# controller.net
KiCad netlist of a schematic drawn in EAGLE
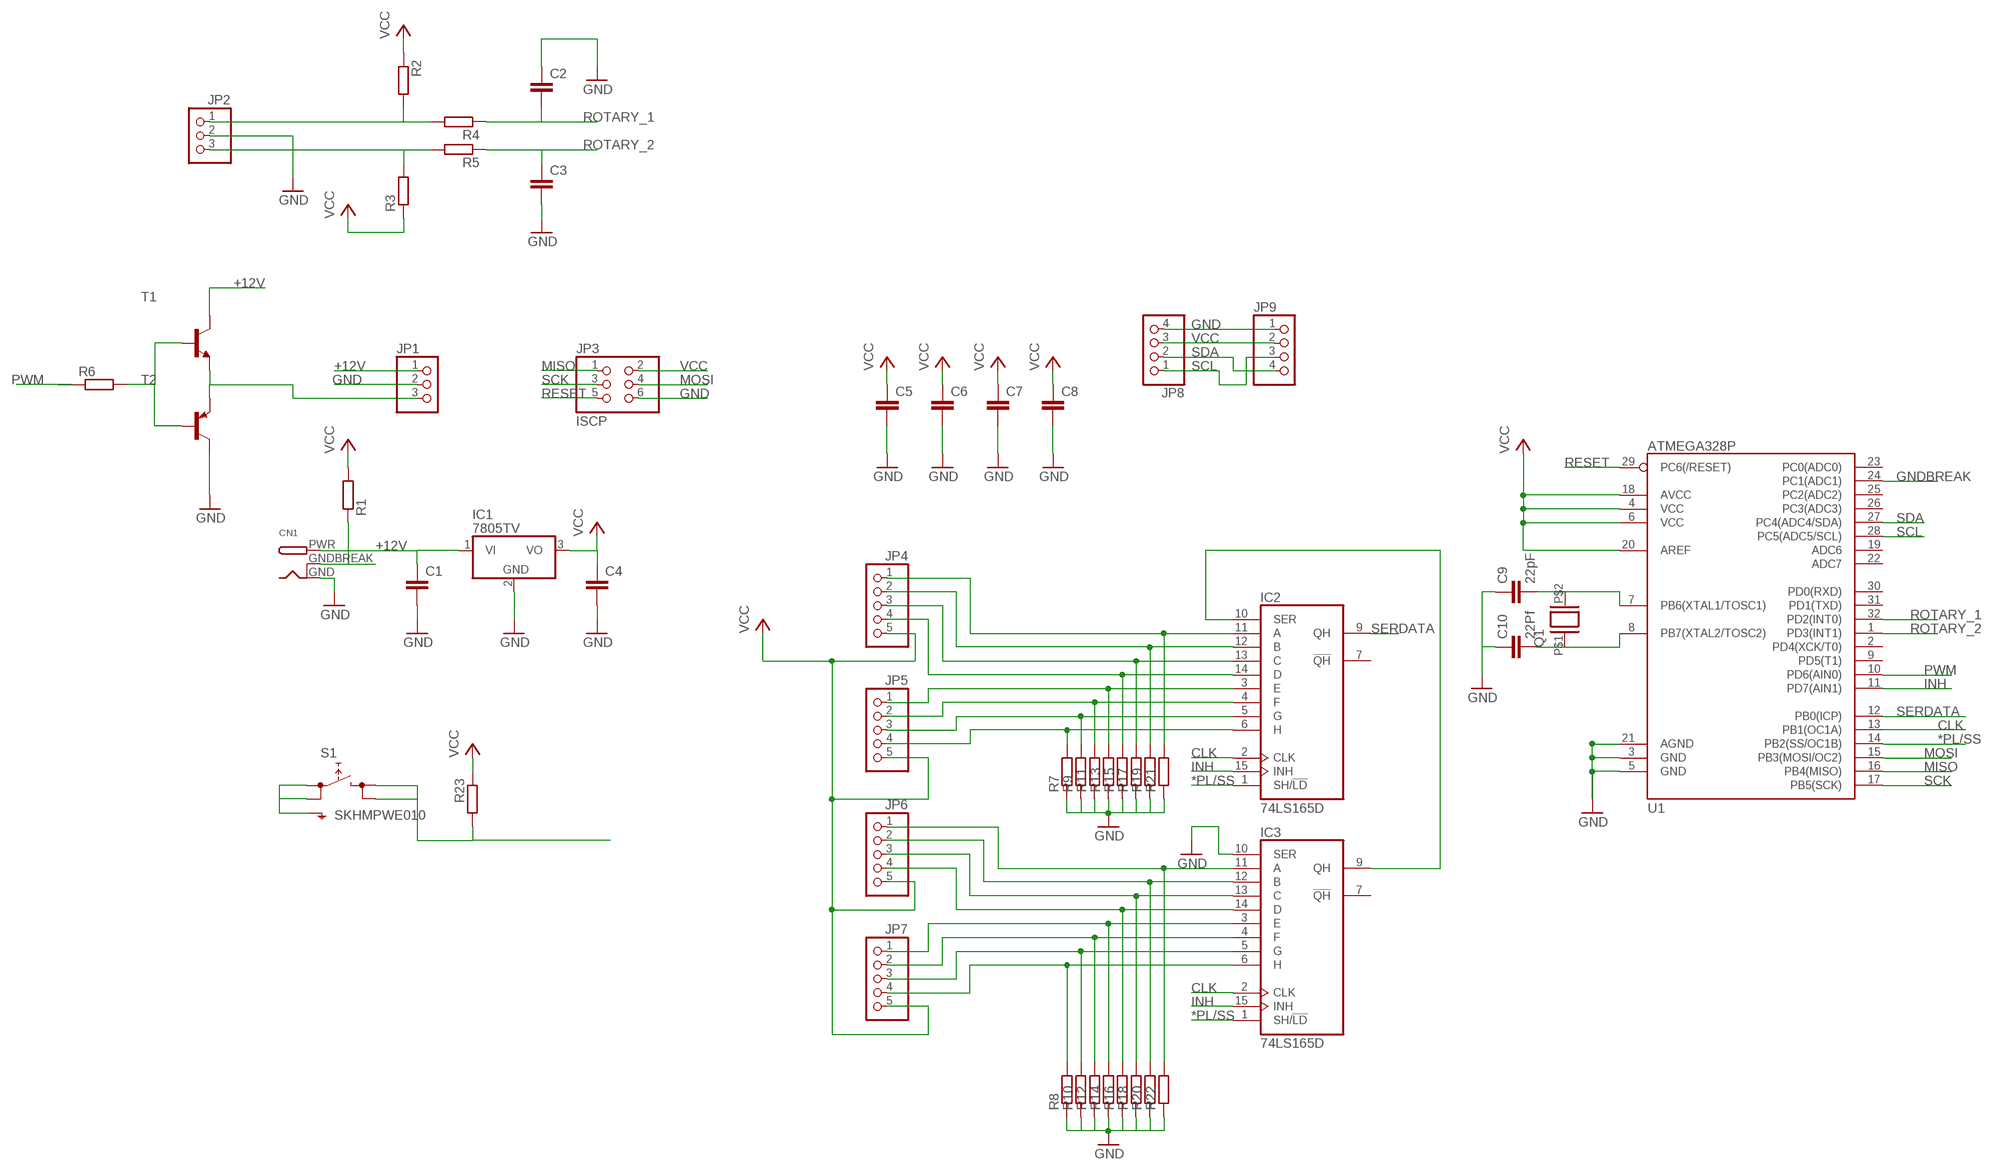
[diagram p0: schematic, sheet 1]

(export (version "E")
  (design (tool "Eeschema 10.0.6"))
  (components
    (comp (ref "C1")
      (value "C-EUC0805")
      (footprint "eagle-import:C0805")
      (libsource (lib "eagle-import") (part "C-EUC0805"))
    )
    (comp (ref "C2")
      (value "C-EUC0805")
      (footprint "eagle-import:C0805")
      (libsource (lib "eagle-import") (part "C-EUC0805"))
    )
    (comp (ref "C3")
      (value "C-EUC0805")
      (footprint "eagle-import:C0805")
      (libsource (lib "eagle-import") (part "C-EUC0805"))
    )
    (comp (ref "C4")
      (value "C-EUC0805")
      (footprint "eagle-import:C0805")
      (libsource (lib "eagle-import") (part "C-EUC0805"))
    )
    (comp (ref "C5")
      (value "C-EUC0805")
      (footprint "eagle-import:C0805")
      (libsource (lib "eagle-import") (part "C-EUC0805"))
    )
    (comp (ref "C6")
      (value "C-EUC0805")
      (footprint "eagle-import:C0805")
      (libsource (lib "eagle-import") (part "C-EUC0805"))
    )
    (comp (ref "C7")
      (value "C-EUC0805")
      (footprint "eagle-import:C0805")
      (libsource (lib "eagle-import") (part "C-EUC0805"))
    )
    (comp (ref "C8")
      (value "C-EUC0805")
      (footprint "eagle-import:C0805")
      (libsource (lib "eagle-import") (part "C-EUC0805"))
    )
    (comp (ref "C9")
      (value "22pF")
      (footprint "eagle-import:C0805")
      (libsource (lib "eagle-import") (part "C-EUC0805"))
    )
    (comp (ref "C10")
      (value "22Pf")
      (footprint "eagle-import:C0805")
      (libsource (lib "eagle-import") (part "C-EUC0805"))
    )
    (comp (ref "CN1")
      (value "DCBARRELPTH")
      (footprint "eagle-import:DCJACK_2MM_PTH")
      (libsource (lib "eagle-import") (part "DCBARRELPTH"))
    )
    (comp (ref "IC1")
      (value "7805TV")
      (footprint "eagle-import:TO220V")
      (libsource (lib "eagle-import") (part "78TV05"))
    )
    (comp (ref "IC2")
      (value "74LS165D")
      (footprint "eagle-import:SO16")
      (libsource (lib "eagle-import") (part "74165DLS"))
    )
    (comp (ref "IC3")
      (value "74LS165D")
      (footprint "eagle-import:SO16")
      (libsource (lib "eagle-import") (part "74165DLS"))
    )
    (comp (ref "JP1")
      (value "PINHD-1X3")
      (footprint "eagle-import:1X03")
      (libsource (lib "eagle-import") (part "PINHD-1X3"))
    )
    (comp (ref "JP2")
      (value "PINHD-1X3")
      (footprint "eagle-import:1X03")
      (libsource (lib "eagle-import") (part "PINHD-1X3"))
    )
    (comp (ref "JP3")
      (value "ISCP")
      (footprint "eagle-import:2X03")
      (libsource (lib "eagle-import") (part "PINHD-2X3"))
    )
    (comp (ref "JP4")
      (value "PINHD-1X5")
      (footprint "eagle-import:1X05")
      (libsource (lib "eagle-import") (part "PINHD-1X5"))
    )
    (comp (ref "JP5")
      (value "PINHD-1X5")
      (footprint "eagle-import:1X05")
      (libsource (lib "eagle-import") (part "PINHD-1X5"))
    )
    (comp (ref "JP6")
      (value "PINHD-1X5")
      (footprint "eagle-import:1X05")
      (libsource (lib "eagle-import") (part "PINHD-1X5"))
    )
    (comp (ref "JP7")
      (value "PINHD-1X5")
      (footprint "eagle-import:1X05")
      (libsource (lib "eagle-import") (part "PINHD-1X5"))
    )
    (comp (ref "JP8")
      (value "PINHD-1X4")
      (footprint "eagle-import:1X04")
      (libsource (lib "eagle-import") (part "PINHD-1X4"))
    )
    (comp (ref "JP9")
      (value "PINHD-1X4")
      (footprint "eagle-import:1X04")
      (libsource (lib "eagle-import") (part "PINHD-1X4"))
    )
    (comp (ref "Q1")
      (value "XTAL")
      (footprint "eagle-import:CSM-3X")
      (libsource (lib "eagle-import") (part "XTAL"))
    )
    (comp (ref "R1")
      (value "R-EU_R0805")
      (footprint "eagle-import:R0805")
      (libsource (lib "eagle-import") (part "R-EU_R0805"))
    )
    (comp (ref "R2")
      (value "R-EU_R0805")
      (footprint "eagle-import:R0805")
      (libsource (lib "eagle-import") (part "R-EU_R0805"))
    )
    (comp (ref "R3")
      (value "R-EU_R0805")
      (footprint "eagle-import:R0805")
      (libsource (lib "eagle-import") (part "R-EU_R0805"))
    )
    (comp (ref "R4")
      (value "R-EU_R0805")
      (footprint "eagle-import:R0805")
      (libsource (lib "eagle-import") (part "R-EU_R0805"))
    )
    (comp (ref "R5")
      (value "R-EU_R0805")
      (footprint "eagle-import:R0805")
      (libsource (lib "eagle-import") (part "R-EU_R0805"))
    )
    (comp (ref "R6")
      (value "R-EU_R0805")
      (footprint "eagle-import:R0805")
      (libsource (lib "eagle-import") (part "R-EU_R0805"))
    )
    (comp (ref "R7")
      (value "R-EU_R0805")
      (footprint "eagle-import:R0805")
      (libsource (lib "eagle-import") (part "R-EU_R0805"))
    )
    (comp (ref "R8")
      (value "R-EU_R0805")
      (footprint "eagle-import:R0805")
      (libsource (lib "eagle-import") (part "R-EU_R0805"))
    )
    (comp (ref "R9")
      (value "R-EU_R0805")
      (footprint "eagle-import:R0805")
      (libsource (lib "eagle-import") (part "R-EU_R0805"))
    )
    (comp (ref "R10")
      (value "R-EU_R0805")
      (footprint "eagle-import:R0805")
      (libsource (lib "eagle-import") (part "R-EU_R0805"))
    )
    (comp (ref "R11")
      (value "R-EU_R0805")
      (footprint "eagle-import:R0805")
      (libsource (lib "eagle-import") (part "R-EU_R0805"))
    )
    (comp (ref "R12")
      (value "R-EU_R0805")
      (footprint "eagle-import:R0805")
      (libsource (lib "eagle-import") (part "R-EU_R0805"))
    )
    (comp (ref "R13")
      (value "R-EU_R0805")
      (footprint "eagle-import:R0805")
      (libsource (lib "eagle-import") (part "R-EU_R0805"))
    )
    (comp (ref "R14")
      (value "R-EU_R0805")
      (footprint "eagle-import:R0805")
      (libsource (lib "eagle-import") (part "R-EU_R0805"))
    )
    (comp (ref "R15")
      (value "R-EU_R0805")
      (footprint "eagle-import:R0805")
      (libsource (lib "eagle-import") (part "R-EU_R0805"))
    )
    (comp (ref "R16")
      (value "R-EU_R0805")
      (footprint "eagle-import:R0805")
      (libsource (lib "eagle-import") (part "R-EU_R0805"))
    )
    (comp (ref "R17")
      (value "R-EU_R0805")
      (footprint "eagle-import:R0805")
      (libsource (lib "eagle-import") (part "R-EU_R0805"))
    )
    (comp (ref "R18")
      (value "R-EU_R0805")
      (footprint "eagle-import:R0805")
      (libsource (lib "eagle-import") (part "R-EU_R0805"))
    )
    (comp (ref "R19")
      (value "R-EU_R0805")
      (footprint "eagle-import:R0805")
      (libsource (lib "eagle-import") (part "R-EU_R0805"))
    )
    (comp (ref "R20")
      (value "R-EU_R0805")
      (footprint "eagle-import:R0805")
      (libsource (lib "eagle-import") (part "R-EU_R0805"))
    )
    (comp (ref "R21")
      (value "R-EU_R0805")
      (footprint "eagle-import:R0805")
      (libsource (lib "eagle-import") (part "R-EU_R0805"))
    )
    (comp (ref "R22")
      (value "R-EU_R0805")
      (footprint "eagle-import:R0805")
      (libsource (lib "eagle-import") (part "R-EU_R0805"))
    )
    (comp (ref "R23")
      (value "R-EU_R0805")
      (footprint "eagle-import:R0805")
      (libsource (lib "eagle-import") (part "R-EU_R0805"))
    )
    (comp (ref "S1")
      (value "SKHMPWE010")
      (footprint "eagle-import:SKHMPXE010")
      (libsource (lib "eagle-import") (part "SKHMPE010W"))
    )
    (comp (ref "T1")
      (value "BC847-NPN-SOT23-BEC")
      (footprint "eagle-import:SOT23-BEC")
      (libsource (lib "eagle-import") (part "-NPN-SOT23-BECBC847"))
    )
    (comp (ref "T2")
      (value "BC807-16-PNP-SOT23-BEC")
      (footprint "eagle-import:SOT23-BEC")
      (libsource (lib "eagle-import") (part "-PNP-SOT23-BECBC807-16"))
    )
    (comp (ref "U1")
      (value "ATMEGA328P")
      (footprint "eagle-import:TQFP32-08")
      (libsource (lib "eagle-import") (part "ATMEGA328_SMT"))
    )
  )
  (nets
    (net (code "1") (name "/*PL{slash}SS") (class "Default")
      (node (ref "IC2") (pin "1") (pinfunction "SH/~{LD}_1") (pintype "input"))
      (node (ref "IC3") (pin "1") (pinfunction "SH/~{LD}_1") (pintype "input"))
      (node (ref "U1") (pin "14") (pinfunction "PB2(SS/OC1B)_14") (pintype "bidirectional"))
    )
    (net (code "2") (name "/+12V") (class "Default")
      (node (ref "C1") (pin "1") (pinfunction "1_1") (pintype "passive"))
      (node (ref "CN1") (pin "PWR") (pinfunction "PWR_PWR") (pintype "power_in"))
      (node (ref "IC1") (pin "1") (pinfunction "VI_1") (pintype "input"))
      (node (ref "JP1") (pin "1") (pinfunction "1_1") (pintype "passive"))
      (node (ref "T1") (pin "C") (pinfunction "C_C") (pintype "passive"))
    )
    (net (code "3") (name "/CLK") (class "Default")
      (node (ref "IC2") (pin "2") (pinfunction "CLK_2") (pintype "input"))
      (node (ref "IC3") (pin "2") (pinfunction "CLK_2") (pintype "input"))
      (node (ref "U1") (pin "13") (pinfunction "PB1(OC1A)_13") (pintype "bidirectional"))
    )
    (net (code "4") (name "/GNDBREAK") (class "Default")
      (node (ref "CN1") (pin "GNDBREAK") (pinfunction "GNDBREAK_GNDBREAK") (pintype "power_in"))
      (node (ref "R1") (pin "1") (pinfunction "1_1") (pintype "passive"))
      (node (ref "U1") (pin "24") (pinfunction "PC1(ADC1)_24") (pintype "bidirectional"))
    )
    (net (code "5") (name "/INH") (class "Default")
      (node (ref "IC2") (pin "15") (pinfunction "INH_15") (pintype "input"))
      (node (ref "IC3") (pin "15") (pinfunction "INH_15") (pintype "input"))
      (node (ref "U1") (pin "11") (pinfunction "PD7(AIN1)_11") (pintype "bidirectional"))
    )
    (net (code "6") (name "/MISO") (class "Default")
      (node (ref "JP3") (pin "1") (pinfunction "1_1") (pintype "passive"))
      (node (ref "U1") (pin "16") (pinfunction "PB4(MISO)_16") (pintype "bidirectional"))
    )
    (net (code "7") (name "/MOSI") (class "Default")
      (node (ref "JP3") (pin "4") (pinfunction "4_4") (pintype "passive"))
      (node (ref "U1") (pin "15") (pinfunction "PB3(MOSI/OC2)_15") (pintype "bidirectional"))
    )
    (net (code "8") (name "/PWM") (class "Default")
      (node (ref "R6") (pin "1") (pinfunction "1_1") (pintype "passive"))
      (node (ref "U1") (pin "10") (pinfunction "PD6(AIN0)_10") (pintype "bidirectional"))
    )
    (net (code "9") (name "/RESET") (class "Default")
      (node (ref "JP3") (pin "5") (pinfunction "5_5") (pintype "passive"))
      (node (ref "R23") (pin "2") (pinfunction "2_2") (pintype "passive"))
      (node (ref "S1") (pin "3") (pinfunction "2.1_3") (pintype "passive"))
      (node (ref "S1") (pin "4") (pinfunction "2.2_4") (pintype "passive"))
      (node (ref "U1") (pin "29") (pinfunction "PC6(/RESET)_29") (pintype "bidirectional"))
    )
    (net (code "10") (name "/ROTARY_1") (class "Default")
      (node (ref "C2") (pin "2") (pinfunction "2_2") (pintype "passive"))
      (node (ref "R4") (pin "1") (pinfunction "1_1") (pintype "passive"))
      (node (ref "U1") (pin "32") (pinfunction "PD2(INT0)_32") (pintype "bidirectional"))
    )
    (net (code "11") (name "/ROTARY_2") (class "Default")
      (node (ref "C3") (pin "1") (pinfunction "1_1") (pintype "passive"))
      (node (ref "R5") (pin "1") (pinfunction "1_1") (pintype "passive"))
      (node (ref "U1") (pin "1") (pinfunction "PD3(INT1)_1") (pintype "bidirectional"))
    )
    (net (code "12") (name "/SCK") (class "Default")
      (node (ref "JP3") (pin "3") (pinfunction "3_3") (pintype "passive"))
      (node (ref "U1") (pin "17") (pinfunction "PB5(SCK)_17") (pintype "bidirectional"))
    )
    (net (code "13") (name "/SCL") (class "Default")
      (node (ref "JP8") (pin "1") (pinfunction "1_1") (pintype "passive"))
      (node (ref "JP9") (pin "3") (pinfunction "3_3") (pintype "passive"))
      (node (ref "U1") (pin "28") (pinfunction "PC5(ADC5/SCL)_28") (pintype "bidirectional"))
    )
    (net (code "14") (name "/SDA") (class "Default")
      (node (ref "JP8") (pin "2") (pinfunction "2_2") (pintype "passive"))
      (node (ref "JP9") (pin "4") (pinfunction "4_4") (pintype "passive"))
      (node (ref "U1") (pin "27") (pinfunction "PC4(ADC4/SDA)_27") (pintype "bidirectional"))
    )
    (net (code "15") (name "/SERDATA") (class "Default")
      (node (ref "IC2") (pin "9") (pinfunction "QH_9") (pintype "output"))
      (node (ref "U1") (pin "12") (pinfunction "PB0(ICP)_12") (pintype "bidirectional"))
    )
    (net (code "16") (name "GND") (class "Default")
      (node (ref "C1") (pin "2") (pinfunction "2_2") (pintype "passive"))
      (node (ref "C10") (pin "1") (pinfunction "1_1") (pintype "passive"))
      (node (ref "C2") (pin "1") (pinfunction "1_1") (pintype "passive"))
      (node (ref "C3") (pin "2") (pinfunction "2_2") (pintype "passive"))
      (node (ref "C4") (pin "2") (pinfunction "2_2") (pintype "passive"))
      (node (ref "C5") (pin "2") (pinfunction "2_2") (pintype "passive"))
      (node (ref "C6") (pin "2") (pinfunction "2_2") (pintype "passive"))
      (node (ref "C7") (pin "2") (pinfunction "2_2") (pintype "passive"))
      (node (ref "C8") (pin "2") (pinfunction "2_2") (pintype "passive"))
      (node (ref "C9") (pin "1") (pinfunction "1_1") (pintype "passive"))
      (node (ref "CN1") (pin "GND") (pinfunction "GND_GND") (pintype "power_in"))
      (node (ref "IC1") (pin "2") (pinfunction "GND_2") (pintype "passive"))
      (node (ref "IC3") (pin "10") (pinfunction "SER_10") (pintype "input"))
      (node (ref "JP1") (pin "2") (pinfunction "2_2") (pintype "passive"))
      (node (ref "JP2") (pin "2") (pinfunction "2_2") (pintype "passive"))
      (node (ref "JP3") (pin "6") (pinfunction "6_6") (pintype "passive"))
      (node (ref "JP8") (pin "4") (pinfunction "4_4") (pintype "passive"))
      (node (ref "JP9") (pin "1") (pinfunction "1_1") (pintype "passive"))
      (node (ref "R10") (pin "1") (pinfunction "1_1") (pintype "passive"))
      (node (ref "R11") (pin "1") (pinfunction "1_1") (pintype "passive"))
      (node (ref "R12") (pin "1") (pinfunction "1_1") (pintype "passive"))
      (node (ref "R13") (pin "1") (pinfunction "1_1") (pintype "passive"))
      (node (ref "R14") (pin "1") (pinfunction "1_1") (pintype "passive"))
      (node (ref "R15") (pin "1") (pinfunction "1_1") (pintype "passive"))
      (node (ref "R16") (pin "1") (pinfunction "1_1") (pintype "passive"))
      (node (ref "R17") (pin "1") (pinfunction "1_1") (pintype "passive"))
      (node (ref "R18") (pin "1") (pinfunction "1_1") (pintype "passive"))
      (node (ref "R19") (pin "1") (pinfunction "1_1") (pintype "passive"))
      (node (ref "R20") (pin "1") (pinfunction "1_1") (pintype "passive"))
      (node (ref "R21") (pin "1") (pinfunction "1_1") (pintype "passive"))
      (node (ref "R22") (pin "1") (pinfunction "1_1") (pintype "passive"))
      (node (ref "R7") (pin "1") (pinfunction "1_1") (pintype "passive"))
      (node (ref "R8") (pin "1") (pinfunction "1_1") (pintype "passive"))
      (node (ref "R9") (pin "1") (pinfunction "1_1") (pintype "passive"))
      (node (ref "S1") (pin "1") (pinfunction "1.1_1") (pintype "passive"))
      (node (ref "S1") (pin "2") (pinfunction "1.2_2") (pintype "passive"))
      (node (ref "S1") (pin "5") (pinfunction "SH_5") (pintype "passive"))
      (node (ref "T2") (pin "C") (pinfunction "C_C") (pintype "passive"))
      (node (ref "U1") (pin "21") (pinfunction "AGND_21") (pintype "bidirectional"))
      (node (ref "U1") (pin "3") (pinfunction "GND_3") (pintype "bidirectional"))
      (node (ref "U1") (pin "5") (pinfunction "GND_5") (pintype "bidirectional"))
    )
    (net (code "17") (name "Net-(IC2A-A)") (class "Default")
      (node (ref "IC2") (pin "11") (pinfunction "A_11") (pintype "input"))
      (node (ref "JP4") (pin "1") (pinfunction "1_1") (pintype "passive"))
      (node (ref "R21") (pin "2") (pinfunction "2_2") (pintype "passive"))
    )
    (net (code "18") (name "Net-(IC2A-B)") (class "Default")
      (node (ref "IC2") (pin "12") (pinfunction "B_12") (pintype "input"))
      (node (ref "JP4") (pin "2") (pinfunction "2_2") (pintype "passive"))
      (node (ref "R19") (pin "2") (pinfunction "2_2") (pintype "passive"))
    )
    (net (code "19") (name "Net-(IC2A-C)") (class "Default")
      (node (ref "IC2") (pin "13") (pinfunction "C_13") (pintype "input"))
      (node (ref "JP4") (pin "3") (pinfunction "3_3") (pintype "passive"))
      (node (ref "R17") (pin "2") (pinfunction "2_2") (pintype "passive"))
    )
    (net (code "20") (name "Net-(IC2A-D)") (class "Default")
      (node (ref "IC2") (pin "14") (pinfunction "D_14") (pintype "input"))
      (node (ref "JP4") (pin "4") (pinfunction "4_4") (pintype "passive"))
      (node (ref "R15") (pin "2") (pinfunction "2_2") (pintype "passive"))
    )
    (net (code "21") (name "Net-(IC2A-E)") (class "Default")
      (node (ref "IC2") (pin "3") (pinfunction "E_3") (pintype "input"))
      (node (ref "JP5") (pin "1") (pinfunction "1_1") (pintype "passive"))
      (node (ref "R13") (pin "2") (pinfunction "2_2") (pintype "passive"))
    )
    (net (code "22") (name "Net-(IC2A-F)") (class "Default")
      (node (ref "IC2") (pin "4") (pinfunction "F_4") (pintype "input"))
      (node (ref "JP5") (pin "2") (pinfunction "2_2") (pintype "passive"))
      (node (ref "R11") (pin "2") (pinfunction "2_2") (pintype "passive"))
    )
    (net (code "23") (name "Net-(IC2A-G)") (class "Default")
      (node (ref "IC2") (pin "5") (pinfunction "G_5") (pintype "input"))
      (node (ref "JP5") (pin "3") (pinfunction "3_3") (pintype "passive"))
      (node (ref "R9") (pin "2") (pinfunction "2_2") (pintype "passive"))
    )
    (net (code "24") (name "Net-(IC2A-H)") (class "Default")
      (node (ref "IC2") (pin "6") (pinfunction "H_6") (pintype "input"))
      (node (ref "JP5") (pin "4") (pinfunction "4_4") (pintype "passive"))
      (node (ref "R7") (pin "2") (pinfunction "2_2") (pintype "passive"))
    )
    (net (code "25") (name "Net-(IC2A-SER)") (class "Default")
      (node (ref "IC2") (pin "10") (pinfunction "SER_10") (pintype "input"))
      (node (ref "IC3") (pin "9") (pinfunction "QH_9") (pintype "output"))
    )
    (net (code "26") (name "Net-(IC3A-A)") (class "Default")
      (node (ref "IC3") (pin "11") (pinfunction "A_11") (pintype "input"))
      (node (ref "JP6") (pin "1") (pinfunction "1_1") (pintype "passive"))
      (node (ref "R22") (pin "2") (pinfunction "2_2") (pintype "passive"))
    )
    (net (code "27") (name "Net-(IC3A-B)") (class "Default")
      (node (ref "IC3") (pin "12") (pinfunction "B_12") (pintype "input"))
      (node (ref "JP6") (pin "2") (pinfunction "2_2") (pintype "passive"))
      (node (ref "R20") (pin "2") (pinfunction "2_2") (pintype "passive"))
    )
    (net (code "28") (name "Net-(IC3A-C)") (class "Default")
      (node (ref "IC3") (pin "13") (pinfunction "C_13") (pintype "input"))
      (node (ref "JP6") (pin "3") (pinfunction "3_3") (pintype "passive"))
      (node (ref "R18") (pin "2") (pinfunction "2_2") (pintype "passive"))
    )
    (net (code "29") (name "Net-(IC3A-D)") (class "Default")
      (node (ref "IC3") (pin "14") (pinfunction "D_14") (pintype "input"))
      (node (ref "JP6") (pin "4") (pinfunction "4_4") (pintype "passive"))
      (node (ref "R16") (pin "2") (pinfunction "2_2") (pintype "passive"))
    )
    (net (code "30") (name "Net-(IC3A-E)") (class "Default")
      (node (ref "IC3") (pin "3") (pinfunction "E_3") (pintype "input"))
      (node (ref "JP7") (pin "1") (pinfunction "1_1") (pintype "passive"))
      (node (ref "R14") (pin "2") (pinfunction "2_2") (pintype "passive"))
    )
    (net (code "31") (name "Net-(IC3A-F)") (class "Default")
      (node (ref "IC3") (pin "4") (pinfunction "F_4") (pintype "input"))
      (node (ref "JP7") (pin "2") (pinfunction "2_2") (pintype "passive"))
      (node (ref "R12") (pin "2") (pinfunction "2_2") (pintype "passive"))
    )
    (net (code "32") (name "Net-(IC3A-G)") (class "Default")
      (node (ref "IC3") (pin "5") (pinfunction "G_5") (pintype "input"))
      (node (ref "JP7") (pin "3") (pinfunction "3_3") (pintype "passive"))
      (node (ref "R10") (pin "2") (pinfunction "2_2") (pintype "passive"))
    )
    (net (code "33") (name "Net-(IC3A-H)") (class "Default")
      (node (ref "IC3") (pin "6") (pinfunction "H_6") (pintype "input"))
      (node (ref "JP7") (pin "4") (pinfunction "4_4") (pintype "passive"))
      (node (ref "R8") (pin "2") (pinfunction "2_2") (pintype "passive"))
    )
    (net (code "34") (name "Net-(JP1-Pad3)") (class "Default")
      (node (ref "JP1") (pin "3") (pinfunction "3_3") (pintype "passive"))
      (node (ref "T1") (pin "E") (pinfunction "E_E") (pintype "passive"))
      (node (ref "T2") (pin "E") (pinfunction "E_E") (pintype "passive"))
    )
    (net (code "35") (name "Net-(JP2-Pad1)") (class "Default")
      (node (ref "JP2") (pin "1") (pinfunction "1_1") (pintype "passive"))
      (node (ref "R2") (pin "2") (pinfunction "2_2") (pintype "passive"))
      (node (ref "R4") (pin "2") (pinfunction "2_2") (pintype "passive"))
    )
    (net (code "36") (name "Net-(JP2-Pad3)") (class "Default")
      (node (ref "JP2") (pin "3") (pinfunction "3_3") (pintype "passive"))
      (node (ref "R3") (pin "2") (pinfunction "2_2") (pintype "passive"))
      (node (ref "R5") (pin "2") (pinfunction "2_2") (pintype "passive"))
    )
    (net (code "37") (name "Net-(Q1-1)") (class "Default")
      (node (ref "C10") (pin "2") (pinfunction "2_2") (pintype "passive"))
      (node (ref "Q1") (pin "P$1") (pinfunction "1_P$1") (pintype "passive"))
      (node (ref "U1") (pin "8") (pinfunction "PB7(XTAL2/TOSC2)_8") (pintype "bidirectional"))
    )
    (net (code "38") (name "Net-(Q1-2)") (class "Default")
      (node (ref "C9") (pin "2") (pinfunction "2_2") (pintype "passive"))
      (node (ref "Q1") (pin "P$2") (pinfunction "2_P$2") (pintype "passive"))
      (node (ref "U1") (pin "7") (pinfunction "PB6(XTAL1/TOSC1)_7") (pintype "bidirectional"))
    )
    (net (code "39") (name "Net-(R6-Pad2)") (class "Default")
      (node (ref "R6") (pin "2") (pinfunction "2_2") (pintype "passive"))
      (node (ref "T1") (pin "B") (pinfunction "B_B") (pintype "passive"))
      (node (ref "T2") (pin "B") (pinfunction "B_B") (pintype "passive"))
    )
    (net (code "40") (name "VCC") (class "Default")
      (node (ref "C4") (pin "1") (pinfunction "1_1") (pintype "passive"))
      (node (ref "C5") (pin "1") (pinfunction "1_1") (pintype "passive"))
      (node (ref "C6") (pin "1") (pinfunction "1_1") (pintype "passive"))
      (node (ref "C7") (pin "1") (pinfunction "1_1") (pintype "passive"))
      (node (ref "C8") (pin "1") (pinfunction "1_1") (pintype "passive"))
      (node (ref "IC1") (pin "3") (pinfunction "VO_3") (pintype "passive"))
      (node (ref "JP3") (pin "2") (pinfunction "2_2") (pintype "passive"))
      (node (ref "JP4") (pin "5") (pinfunction "5_5") (pintype "passive"))
      (node (ref "JP5") (pin "5") (pinfunction "5_5") (pintype "passive"))
      (node (ref "JP6") (pin "5") (pinfunction "5_5") (pintype "passive"))
      (node (ref "JP7") (pin "5") (pinfunction "5_5") (pintype "passive"))
      (node (ref "JP8") (pin "3") (pinfunction "3_3") (pintype "passive"))
      (node (ref "JP9") (pin "2") (pinfunction "2_2") (pintype "passive"))
      (node (ref "R1") (pin "2") (pinfunction "2_2") (pintype "passive"))
      (node (ref "R2") (pin "1") (pinfunction "1_1") (pintype "passive"))
      (node (ref "R23") (pin "1") (pinfunction "1_1") (pintype "passive"))
      (node (ref "R3") (pin "1") (pinfunction "1_1") (pintype "passive"))
      (node (ref "U1") (pin "18") (pinfunction "AVCC_18") (pintype "bidirectional"))
      (node (ref "U1") (pin "20") (pinfunction "AREF_20") (pintype "bidirectional"))
      (node (ref "U1") (pin "4") (pinfunction "VCC_4") (pintype "bidirectional"))
      (node (ref "U1") (pin "6") (pinfunction "VCC_6") (pintype "bidirectional"))
    )
    (net (code "41") (name "unconnected-(IC2A-~{QH}-Pad7)") (class "Default")
      (node (ref "IC2") (pin "7") (pinfunction "~{QH}_7") (pintype "output"))
    )
    (net (code "42") (name "unconnected-(IC3A-~{QH}-Pad7)") (class "Default")
      (node (ref "IC3") (pin "7") (pinfunction "~{QH}_7") (pintype "output"))
    )
    (net (code "43") (name "unconnected-(U1-ADC6-Pad19)") (class "Default")
      (node (ref "U1") (pin "19") (pinfunction "ADC6_19") (pintype "bidirectional"))
    )
    (net (code "44") (name "unconnected-(U1-ADC7-Pad22)") (class "Default")
      (node (ref "U1") (pin "22") (pinfunction "ADC7_22") (pintype "bidirectional"))
    )
    (net (code "45") (name "unconnected-(U1-PC0(ADC0)-Pad23)") (class "Default")
      (node (ref "U1") (pin "23") (pinfunction "PC0(ADC0)_23") (pintype "bidirectional"))
    )
    (net (code "46") (name "unconnected-(U1-PC2(ADC2)-Pad25)") (class "Default")
      (node (ref "U1") (pin "25") (pinfunction "PC2(ADC2)_25") (pintype "bidirectional"))
    )
    (net (code "47") (name "unconnected-(U1-PC3(ADC3)-Pad26)") (class "Default")
      (node (ref "U1") (pin "26") (pinfunction "PC3(ADC3)_26") (pintype "bidirectional"))
    )
    (net (code "48") (name "unconnected-(U1-PD0(RXD)-Pad30)") (class "Default")
      (node (ref "U1") (pin "30") (pinfunction "PD0(RXD)_30") (pintype "bidirectional"))
    )
    (net (code "49") (name "unconnected-(U1-PD1(TXD)-Pad31)") (class "Default")
      (node (ref "U1") (pin "31") (pinfunction "PD1(TXD)_31") (pintype "bidirectional"))
    )
    (net (code "50") (name "unconnected-(U1-PD4(XCK{slash}T0)-Pad2)") (class "Default")
      (node (ref "U1") (pin "2") (pinfunction "PD4(XCK/T0)_2") (pintype "bidirectional"))
    )
    (net (code "51") (name "unconnected-(U1-PD5(T1)-Pad9)") (class "Default")
      (node (ref "U1") (pin "9") (pinfunction "PD5(T1)_9") (pintype "bidirectional"))
    )
  )
)
